# Mergen_Telemetri_Ate_leme.net
KiCad netlist of a schematic drawn in EAGLE
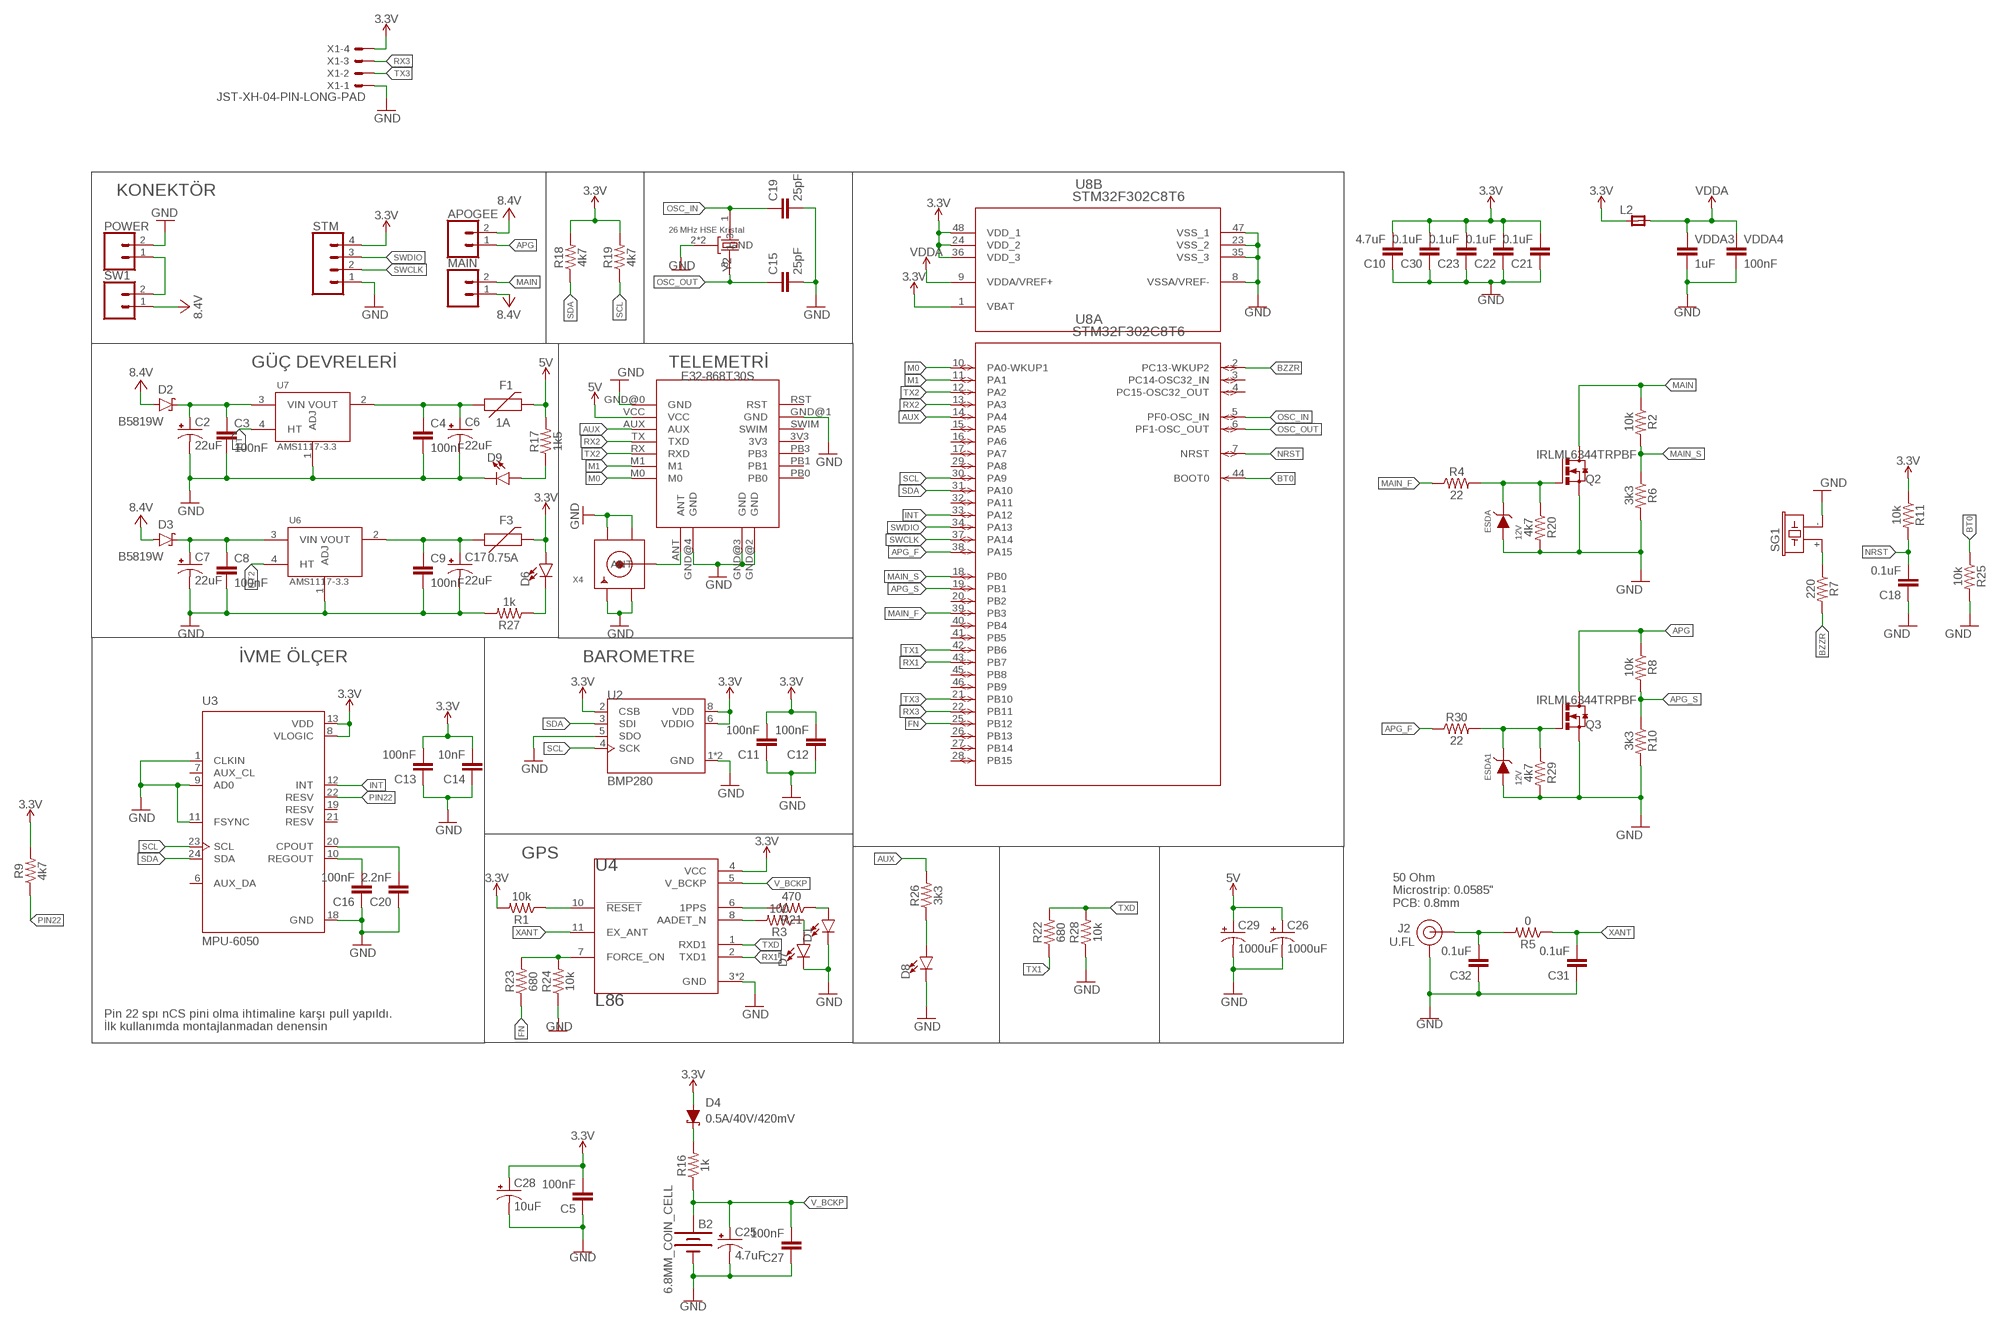
[diagram p0: schematic, sheet 1]

(export (version "E")
  (design (tool "Eeschema 10.0.6"))
  (components
    (comp (ref "APOGEE")
      (value "CONN_023.5MM-NO_SILK")
      (footprint "eagle-import:SCREWTERMINAL-3.5MM-2-NS")
      (libsource (lib "eagle-import") (part "CONN_023.5MM-NO_SILK"))
    )
    (comp (ref "B2")
      (value "6.8MM_COIN_CELL")
      (footprint "eagle-import:BATTCON-6.8MM")
      (libsource (lib "eagle-import") (part "BATTERY-6.8MM_SMD"))
    )
    (comp (ref "C2")
      (value "22uF")
      (footprint "eagle-import:EIA3528")
      (libsource (lib "eagle-import") (part "47UF-POLAR-EIA3528-10V-10%"))
    )
    (comp (ref "C3")
      (value "100nF")
      (footprint "eagle-import:0603")
      (libsource (lib "eagle-import") (part "1.0UF-0603-16V-10%"))
    )
    (comp (ref "C4")
      (value "100nF")
      (footprint "eagle-import:0603")
      (libsource (lib "eagle-import") (part "1.0UF-0603-16V-10%"))
    )
    (comp (ref "C5")
      (value "100nF")
      (footprint "eagle-import:0603")
      (libsource (lib "eagle-import") (part "1.0UF-0603-16V-10%"))
    )
    (comp (ref "C6")
      (value "22uF")
      (footprint "eagle-import:EIA3528")
      (libsource (lib "eagle-import") (part "47UF-POLAR-EIA3528-10V-10%"))
    )
    (comp (ref "C7")
      (value "22uF")
      (footprint "eagle-import:EIA3528")
      (libsource (lib "eagle-import") (part "47UF-POLAR-EIA3528-10V-10%"))
    )
    (comp (ref "C8")
      (value "100nF")
      (footprint "eagle-import:0603")
      (libsource (lib "eagle-import") (part "1.0UF-0603-16V-10%"))
    )
    (comp (ref "C9")
      (value "100nF")
      (footprint "eagle-import:0603")
      (libsource (lib "eagle-import") (part "1.0UF-0603-16V-10%"))
    )
    (comp (ref "C10")
      (value "4.7uF")
      (footprint "eagle-import:0603")
      (libsource (lib "eagle-import") (part "1.0UF-0603-16V-10%"))
    )
    (comp (ref "C11")
      (value "100nF")
      (footprint "eagle-import:0603")
      (libsource (lib "eagle-import") (part "1.0UF-0603-16V-10%"))
    )
    (comp (ref "C12")
      (value "100nF")
      (footprint "eagle-import:0603")
      (libsource (lib "eagle-import") (part "1.0UF-0603-16V-10%"))
    )
    (comp (ref "C13")
      (value "100nF")
      (footprint "eagle-import:0603")
      (libsource (lib "eagle-import") (part "1.0UF-0603-16V-10%"))
    )
    (comp (ref "C14")
      (value "10nF")
      (footprint "eagle-import:0603")
      (libsource (lib "eagle-import") (part "1.0UF-0603-16V-10%"))
    )
    (comp (ref "C15")
      (value "25pF")
      (footprint "eagle-import:0603")
      (libsource (lib "eagle-import") (part "1.0UF-0603-16V-10%"))
    )
    (comp (ref "C16")
      (value "100nF")
      (footprint "eagle-import:0603")
      (libsource (lib "eagle-import") (part "1.0UF-0603-16V-10%"))
    )
    (comp (ref "C17")
      (value "22uF")
      (footprint "eagle-import:EIA3528")
      (libsource (lib "eagle-import") (part "47UF-POLAR-EIA3528-10V-10%"))
    )
    (comp (ref "C18")
      (value "0.1uF")
      (footprint "eagle-import:0603")
      (libsource (lib "eagle-import") (part "1.0UF-0603-16V-10%"))
    )
    (comp (ref "C19")
      (value "25pF")
      (footprint "eagle-import:0603")
      (libsource (lib "eagle-import") (part "1.0UF-0603-16V-10%"))
    )
    (comp (ref "C20")
      (value "2.2nF")
      (footprint "eagle-import:0603")
      (libsource (lib "eagle-import") (part "1.0UF-0603-16V-10%"))
    )
    (comp (ref "C21")
      (value "0.1uF")
      (footprint "eagle-import:0603")
      (libsource (lib "eagle-import") (part "1.0UF-0603-16V-10%"))
    )
    (comp (ref "C22")
      (value "0.1uF")
      (footprint "eagle-import:0603")
      (libsource (lib "eagle-import") (part "1.0UF-0603-16V-10%"))
    )
    (comp (ref "C23")
      (value "0.1uF")
      (footprint "eagle-import:0603")
      (libsource (lib "eagle-import") (part "1.0UF-0603-16V-10%"))
    )
    (comp (ref "C25")
      (value "4.7uF")
      (footprint "eagle-import:EIA3216")
      (libsource (lib "eagle-import") (part "10UF-POLAR-EIA3216-16V-10%(TANT)"))
    )
    (comp (ref "C26")
      (value "1000uF")
      (footprint "eagle-import:150CLZ-1010")
      (libsource (lib "eagle-import") (part "CPOL-US150CLZ-1010"))
    )
    (comp (ref "C27")
      (value "100nF")
      (footprint "eagle-import:0603")
      (libsource (lib "eagle-import") (part "1.0UF-0603-16V-10%"))
    )
    (comp (ref "C28")
      (value "10uF")
      (footprint "eagle-import:EIA3216")
      (libsource (lib "eagle-import") (part "10UF-POLAR-EIA3216-16V-10%(TANT)"))
    )
    (comp (ref "C29")
      (value "1000uF")
      (footprint "eagle-import:150CLZ-1010")
      (libsource (lib "eagle-import") (part "CPOL-US150CLZ-1010"))
    )
    (comp (ref "C30")
      (value "0.1uF")
      (footprint "eagle-import:0603")
      (libsource (lib "eagle-import") (part "1.0UF-0603-16V-10%"))
    )
    (comp (ref "C31")
      (value "0.1uF")
      (footprint "eagle-import:0603")
      (libsource (lib "eagle-import") (part "1.0UF-0603-16V-10%"))
    )
    (comp (ref "C32")
      (value "0.1uF")
      (footprint "eagle-import:0603")
      (libsource (lib "eagle-import") (part "1.0UF-0603-16V-10%"))
    )
    (comp (ref "D1")
      (value "LED0603")
      (footprint "eagle-import:LED-0603")
      (libsource (lib "eagle-import") (part "LED0603"))
    )
    (comp (ref "D2")
      (value "B5819W")
      (footprint "eagle-import:SODFL3718X115")
      (fields (field (name "MANUFACTURER") "ON Semiconductor") (field (name "MPN") "MBR0520LT1G"))
      (libsource (lib "eagle-import") (part "SCHOTTKY_DO-219MBR0520LT1G"))
    )
    (comp (ref "D3")
      (value "B5819W")
      (footprint "eagle-import:SODFL3718X115")
      (fields (field (name "MANUFACTURER") "ON Semiconductor") (field (name "MPN") "MBR0520LT1G"))
      (libsource (lib "eagle-import") (part "SCHOTTKY_DO-219MBR0520LT1G"))
    )
    (comp (ref "D4")
      (value "0.5A/40V/420mV")
      (footprint "eagle-import:SOD-323")
      (libsource (lib "eagle-import") (part "DIODE-SCHOTTKY-PMEG4005EJ"))
    )
    (comp (ref "D6")
      (value "LED0603")
      (footprint "eagle-import:LED-0603")
      (libsource (lib "eagle-import") (part "LED0603"))
    )
    (comp (ref "D7")
      (value "LED0603")
      (footprint "eagle-import:LED-0603")
      (libsource (lib "eagle-import") (part "LED0603"))
    )
    (comp (ref "D8")
      (value "LED0603")
      (footprint "eagle-import:LED-0603")
      (libsource (lib "eagle-import") (part "LED0603"))
    )
    (comp (ref "D9")
      (value "LED0603")
      (footprint "eagle-import:LED-0603")
      (libsource (lib "eagle-import") (part "LED0603"))
    )
    (comp (ref "ESDA")
      (value "12V")
      (footprint "eagle-import:WE-TVSP_DO-214AC_UNIDIRECTIONAL")
      (libsource (lib "eagle-import") (part "WE-TVSP_DO-214AC_400W_UNI_824500102"))
    )
    (comp (ref "ESDA1")
      (value "12V")
      (footprint "eagle-import:WE-TVSP_DO-214AC_UNIDIRECTIONAL")
      (libsource (lib "eagle-import") (part "WE-TVSP_DO-214AC_400W_UNI_824500102"))
    )
    (comp (ref "F1")
      (value "1A")
      (footprint "eagle-import:1206")
      (libsource (lib "eagle-import") (part "PPTC_HALF-AMP"))
    )
    (comp (ref "F3")
      (value "0.75A")
      (footprint "eagle-import:1206")
      (libsource (lib "eagle-import") (part "PPTC_HALF-AMP"))
    )
    (comp (ref "J2")
      (value "U.FL")
      (footprint "eagle-import:U.FL")
      (libsource (lib "eagle-import") (part "U.FL2PIN"))
    )
    (comp (ref "L2")
      (value "RC-MASTER-SMD_FB_0805MP")
      (footprint "eagle-import:RC-MASTER-SMD_L0805MP")
      (libsource (lib "eagle-import") (part "RC-MASTER-SMD_FB_0805MP"))
    )
    (comp (ref "MAIN")
      (value "CONN_023.5MM-NO_SILK")
      (footprint "eagle-import:SCREWTERMINAL-3.5MM-2-NS")
      (libsource (lib "eagle-import") (part "CONN_023.5MM-NO_SILK"))
    )
    (comp (ref "POWER")
      (value "CONN_023.5MM-NO_SILK")
      (footprint "eagle-import:SCREWTERMINAL-3.5MM-2-NS")
      (libsource (lib "eagle-import") (part "CONN_023.5MM-NO_SILK"))
    )
    (comp (ref "Q2")
      (value "IRLML6344TRPBF")
      (footprint "eagle-import:SOT23")
      (fields (field (name "MF") "Infineon"))
      (libsource (lib "eagle-import") (part "IRLML6344TRPBF"))
    )
    (comp (ref "Q3")
      (value "IRLML6344TRPBF")
      (footprint "eagle-import:SOT23")
      (fields (field (name "MF") "Infineon"))
      (libsource (lib "eagle-import") (part "IRLML6344TRPBF"))
    )
    (comp (ref "R1")
      (value "10k")
      (footprint "eagle-import:0603")
      (libsource (lib "eagle-import") (part "SparkFun-Resistors_532_1KOHM-0603-1/10W-1%"))
    )
    (comp (ref "R2")
      (value "10k")
      (footprint "eagle-import:0603")
      (libsource (lib "eagle-import") (part "SparkFun-Resistors_532_1KOHM-0603-1/10W-1%"))
    )
    (comp (ref "R3")
      (value "100")
      (footprint "eagle-import:0603")
      (libsource (lib "eagle-import") (part "SparkFun-Resistors_532_1KOHM-0603-1/10W-1%"))
    )
    (comp (ref "R4")
      (value "22")
      (footprint "eagle-import:0603")
      (libsource (lib "eagle-import") (part "SparkFun-Resistors_532_1KOHM-0603-1/10W-1%"))
    )
    (comp (ref "R5")
      (value "0")
      (footprint "eagle-import:0603")
      (libsource (lib "eagle-import") (part "SparkFun-Resistors_532_1KOHM-0603-1/10W-1%"))
    )
    (comp (ref "R6")
      (value "3k3")
      (footprint "eagle-import:0603")
      (libsource (lib "eagle-import") (part "SparkFun-Resistors_532_1KOHM-0603-1/10W-1%"))
    )
    (comp (ref "R7")
      (value "220")
      (footprint "eagle-import:0603")
      (libsource (lib "eagle-import") (part "SparkFun-Resistors_532_1KOHM-0603-1/10W-1%"))
    )
    (comp (ref "R8")
      (value "10k")
      (footprint "eagle-import:0603")
      (libsource (lib "eagle-import") (part "SparkFun-Resistors_532_1KOHM-0603-1/10W-1%"))
    )
    (comp (ref "R9")
      (value "4k7")
      (footprint "eagle-import:0603")
      (libsource (lib "eagle-import") (part "SparkFun-Resistors_532_1KOHM-0603-1/10W-1%"))
    )
    (comp (ref "R10")
      (value "3k3")
      (footprint "eagle-import:0603")
      (libsource (lib "eagle-import") (part "SparkFun-Resistors_532_1KOHM-0603-1/10W-1%"))
    )
    (comp (ref "R11")
      (value "10k")
      (footprint "eagle-import:0603")
      (libsource (lib "eagle-import") (part "SparkFun-Resistors_532_1KOHM-0603-1/10W-1%"))
    )
    (comp (ref "R16")
      (value "1k")
      (footprint "eagle-import:0603")
      (libsource (lib "eagle-import") (part "1KOHM-0603-1/10W-1%"))
    )
    (comp (ref "R17")
      (value "1k5")
      (footprint "eagle-import:0603")
      (libsource (lib "eagle-import") (part "SparkFun-Resistors_532_1KOHM-0603-1/10W-1%"))
    )
    (comp (ref "R18")
      (value "4k7")
      (footprint "eagle-import:0603")
      (libsource (lib "eagle-import") (part "SparkFun-Resistors_532_1KOHM-0603-1/10W-1%"))
    )
    (comp (ref "R19")
      (value "4k7")
      (footprint "eagle-import:0603")
      (libsource (lib "eagle-import") (part "SparkFun-Resistors_532_1KOHM-0603-1/10W-1%"))
    )
    (comp (ref "R20")
      (value "4k7")
      (footprint "eagle-import:0603")
      (libsource (lib "eagle-import") (part "SparkFun-Resistors_532_1KOHM-0603-1/10W-1%"))
    )
    (comp (ref "R21")
      (value "470")
      (footprint "eagle-import:0603")
      (libsource (lib "eagle-import") (part "SparkFun-Resistors_532_1KOHM-0603-1/10W-1%"))
    )
    (comp (ref "R22")
      (value "680")
      (footprint "eagle-import:0603")
      (libsource (lib "eagle-import") (part "SparkFun-Resistors_532_1KOHM-0603-1/10W-1%"))
    )
    (comp (ref "R23")
      (value "680")
      (footprint "eagle-import:0603")
      (libsource (lib "eagle-import") (part "SparkFun-Resistors_532_1KOHM-0603-1/10W-1%"))
    )
    (comp (ref "R24")
      (value "10k")
      (footprint "eagle-import:0603")
      (libsource (lib "eagle-import") (part "SparkFun-Resistors_532_1KOHM-0603-1/10W-1%"))
    )
    (comp (ref "R25")
      (value "10k")
      (footprint "eagle-import:0603")
      (libsource (lib "eagle-import") (part "SparkFun-Resistors_532_1KOHM-0603-1/10W-1%"))
    )
    (comp (ref "R26")
      (value "3k3")
      (footprint "eagle-import:0603")
      (libsource (lib "eagle-import") (part "SparkFun-Resistors_532_1KOHM-0603-1/10W-1%"))
    )
    (comp (ref "R27")
      (value "1k")
      (footprint "eagle-import:0603")
      (libsource (lib "eagle-import") (part "SparkFun-Resistors_532_1KOHM-0603-1/10W-1%"))
    )
    (comp (ref "R28")
      (value "10k")
      (footprint "eagle-import:0603")
      (libsource (lib "eagle-import") (part "SparkFun-Resistors_532_1KOHM-0603-1/10W-1%"))
    )
    (comp (ref "R29")
      (value "4k7")
      (footprint "eagle-import:0603")
      (libsource (lib "eagle-import") (part "SparkFun-Resistors_532_1KOHM-0603-1/10W-1%"))
    )
    (comp (ref "R30")
      (value "22")
      (footprint "eagle-import:0603")
      (libsource (lib "eagle-import") (part "SparkFun-Resistors_532_1KOHM-0603-1/10W-1%"))
    )
    (comp (ref "SG1")
      (value "F/CM12P")
      (footprint "eagle-import:F_CM12P")
      (libsource (lib "eagle-import") (part "F/CM12P"))
    )
    (comp (ref "STM")
      (value "CONN_04")
      (footprint "eagle-import:1X04")
      (libsource (lib "eagle-import") (part "CONN_04"))
    )
    (comp (ref "SW1")
      (value "CONN_023.5MM-NO_SILK")
      (footprint "eagle-import:SCREWTERMINAL-3.5MM-2-NS")
      (libsource (lib "eagle-import") (part "CONN_023.5MM-NO_SILK"))
    )
    (comp (ref "U2")
      (value "BMP280")
      (footprint "eagle-import:XDCR_BMP280")
      (fields (field (name "MF") "Bosch"))
      (libsource (lib "eagle-import") (part "BMP280"))
    )
    (comp (ref "U3")
      (value "MPU-6050")
      (footprint "eagle-import:QFN50P400X400X95-24N")
      (fields (field (name "MF") "TDK InvenSense"))
      (libsource (lib "eagle-import") (part "MPU-6050"))
    )
    (comp (ref "U4")
      (value "L86")
      (footprint "eagle-import:XCVR_L86")
      (fields (field (name "MF") "Quectel"))
      (libsource (lib "eagle-import") (part "L86"))
    )
    (comp (ref "U5")
      (value "E32-868T30S")
      (footprint "eagle-import:E32-868T30S")
      (libsource (lib "eagle-import") (part "E32-868T30S"))
    )
    (comp (ref "U6")
      (value "AMS1117-3.3")
      (footprint "eagle-import:SOT229P700X180-4N")
      (fields (field (name "MF") "Advanced Monolithic Systems"))
      (libsource (lib "eagle-import") (part "AMS1117-3.3"))
    )
    (comp (ref "U7")
      (value "AMS1117-3.3")
      (footprint "eagle-import:SOT229P700X180-4N")
      (fields (field (name "MF") "Advanced Monolithic Systems"))
      (libsource (lib "eagle-import") (part "AMS1117-3.3"))
    )
    (comp (ref "U8")
      (value "STM32F302C8T6")
      (footprint "eagle-import:LQFP48-7X7MM")
      (fields (field (name "COPYRIGHT") "Copyright (C) 2018 Accelerated Designs. All rights reserved"))
      (libsource (lib "eagle-import") (part "STM32F302C8T6"))
    )
    (comp (ref "VDDA3")
      (value "1uF")
      (footprint "eagle-import:0603")
      (libsource (lib "eagle-import") (part "0.1UF-0603-25V-(+80/-20%)"))
    )
    (comp (ref "VDDA4")
      (value "100nF")
      (footprint "eagle-import:0603")
      (libsource (lib "eagle-import") (part "0.1UF-0603-25V-(+80/-20%)"))
    )
    (comp (ref "X1")
      (value "JST-XH-04-PIN-LONG-PAD")
      (footprint "eagle-import:JST-XH-04-PACKAGE-LONG-PAD")
      (libsource (lib "eagle-import") (part "JST-XH-04-PIN-LONG-PAD"))
    )
    (comp (ref "X4")
      (value "SMACONNECTOR")
      (footprint "eagle-import:SMA90_DIP")
      (libsource (lib "eagle-import") (part "SMACONNECTOR"))
    )
    (comp (ref "Y2")
      (value "ABM3B-26.000MHZ-10-1-U-T")
      (footprint "eagle-import:OSCCC500X320X110-4N")
      (fields (field (name "MF") "Abracon"))
      (libsource (lib "eagle-import") (part "ABM3B-26.000MHZ-10-1-U-T"))
    )
  )
  (nets
    (net (code "1") (name "3.3V") (class "Default")
      (node (ref "C10") (pin "2") (pinfunction "2_2") (pintype "passive"))
      (node (ref "C11") (pin "2") (pinfunction "2_2") (pintype "passive"))
      (node (ref "C12") (pin "2") (pinfunction "2_2") (pintype "passive"))
      (node (ref "C13") (pin "2") (pinfunction "2_2") (pintype "passive"))
      (node (ref "C14") (pin "2") (pinfunction "2_2") (pintype "passive"))
      (node (ref "C21") (pin "2") (pinfunction "2_2") (pintype "passive"))
      (node (ref "C22") (pin "2") (pinfunction "2_2") (pintype "passive"))
      (node (ref "C23") (pin "2") (pinfunction "2_2") (pintype "passive"))
      (node (ref "C28") (pin "+") (pinfunction "+_+") (pintype "passive"))
      (node (ref "C30") (pin "2") (pinfunction "2_2") (pintype "passive"))
      (node (ref "C5") (pin "2") (pinfunction "2_2") (pintype "passive"))
      (node (ref "D4") (pin "A") (pinfunction "A_A") (pintype "passive"))
      (node (ref "D6") (pin "A") (pinfunction "A_A") (pintype "passive"))
      (node (ref "F3") (pin "2") (pinfunction "2_2") (pintype "bidirectional"))
      (node (ref "L2") (pin "1") (pinfunction "1_1") (pintype "passive"))
      (node (ref "R1") (pin "2") (pinfunction "2_2") (pintype "passive"))
      (node (ref "R11") (pin "1") (pinfunction "1_1") (pintype "passive"))
      (node (ref "R18") (pin "2") (pinfunction "2_2") (pintype "passive"))
      (node (ref "R19") (pin "2") (pinfunction "2_2") (pintype "passive"))
      (node (ref "R9") (pin "2") (pinfunction "2_2") (pintype "passive"))
      (node (ref "STM") (pin "4") (pinfunction "4_4") (pintype "passive"))
      (node (ref "U2") (pin "2") (pinfunction "CSB_2") (pintype "input"))
      (node (ref "U2") (pin "6") (pinfunction "VDDIO_6") (pintype "power_in"))
      (node (ref "U2") (pin "8") (pinfunction "VDD_8") (pintype "power_in"))
      (node (ref "U3") (pin "13") (pinfunction "VDD_13") (pintype "power_in"))
      (node (ref "U3") (pin "8") (pinfunction "VLOGIC_8") (pintype "power_in"))
      (node (ref "U4") (pin "4") (pinfunction "VCC_4") (pintype "power_in"))
      (node (ref "U8") (pin "1") (pinfunction "VBAT_1") (pintype "power_in"))
      (node (ref "U8") (pin "24") (pinfunction "VDD_2_24") (pintype "power_in"))
      (node (ref "U8") (pin "36") (pinfunction "VDD_3_36") (pintype "power_in"))
      (node (ref "U8") (pin "48") (pinfunction "VDD_1_48") (pintype "power_in"))
      (node (ref "X1") (pin "4") (pinfunction "S_4") (pintype "passive"))
    )
    (net (code "2") (name "5V") (class "Default")
      (node (ref "C26") (pin "+") (pinfunction "+_+") (pintype "passive"))
      (node (ref "C29") (pin "+") (pinfunction "+_+") (pintype "passive"))
      (node (ref "F1") (pin "2") (pinfunction "2_2") (pintype "bidirectional"))
      (node (ref "R17") (pin "2") (pinfunction "2_2") (pintype "passive"))
      (node (ref "U5") (pin "VCC") (pinfunction "VCC_VCC") (pintype "bidirectional"))
    )
    (net (code "3") (name "8.4V") (class "Default")
      (node (ref "APOGEE") (pin "2") (pinfunction "2_2") (pintype "passive"))
      (node (ref "D2") (pin "2") (pinfunction "A_2") (pintype "passive"))
      (node (ref "D3") (pin "2") (pinfunction "A_2") (pintype "passive"))
      (node (ref "MAIN") (pin "1") (pinfunction "1_1") (pintype "passive"))
      (node (ref "SW1") (pin "1") (pinfunction "1_1") (pintype "passive"))
    )
    (net (code "4") (name "APG") (class "Default")
      (node (ref "APOGEE") (pin "1") (pinfunction "1_1") (pintype "passive"))
      (node (ref "Q3") (pin "3") (pinfunction "D_3") (pintype "passive"))
      (node (ref "R8") (pin "1") (pinfunction "1_1") (pintype "passive"))
    )
    (net (code "5") (name "APG_F") (class "Default")
      (node (ref "R30") (pin "1") (pinfunction "1_1") (pintype "passive"))
      (node (ref "U8") (pin "38") (pinfunction "PA15_38") (pintype "bidirectional"))
    )
    (net (code "6") (name "APG_S") (class "Default")
      (node (ref "R10") (pin "1") (pinfunction "1_1") (pintype "passive"))
      (node (ref "R8") (pin "2") (pinfunction "2_2") (pintype "passive"))
      (node (ref "U8") (pin "19") (pinfunction "PB1_19") (pintype "bidirectional"))
    )
    (net (code "7") (name "AUX") (class "Default")
      (node (ref "R26") (pin "2") (pinfunction "2_2") (pintype "passive"))
      (node (ref "U5") (pin "AUX") (pinfunction "AUX_AUX") (pintype "bidirectional"))
      (node (ref "U8") (pin "14") (pinfunction "PA4_14") (pintype "bidirectional"))
    )
    (net (code "8") (name "BT0") (class "Default")
      (node (ref "R25") (pin "1") (pinfunction "1_1") (pintype "passive"))
      (node (ref "U8") (pin "44") (pinfunction "BOOT0_44") (pintype "input"))
    )
    (net (code "9") (name "BZZR") (class "Default")
      (node (ref "R7") (pin "2") (pinfunction "2_2") (pintype "passive"))
      (node (ref "U8") (pin "2") (pinfunction "PC13-WKUP2_2") (pintype "bidirectional"))
    )
    (net (code "10") (name "FN") (class "Default")
      (node (ref "R23") (pin "1") (pinfunction "1_1") (pintype "passive"))
      (node (ref "U8") (pin "25") (pinfunction "PB12_25") (pintype "bidirectional"))
    )
    (net (code "11") (name "GND") (class "Default")
      (node (ref "B2") (pin "-") (pinfunction "-_-") (pintype "power_in"))
      (node (ref "C10") (pin "1") (pinfunction "1_1") (pintype "passive"))
      (node (ref "C11") (pin "1") (pinfunction "1_1") (pintype "passive"))
      (node (ref "C12") (pin "1") (pinfunction "1_1") (pintype "passive"))
      (node (ref "C13") (pin "1") (pinfunction "1_1") (pintype "passive"))
      (node (ref "C14") (pin "1") (pinfunction "1_1") (pintype "passive"))
      (node (ref "C15") (pin "2") (pinfunction "2_2") (pintype "passive"))
      (node (ref "C16") (pin "1") (pinfunction "1_1") (pintype "passive"))
      (node (ref "C17") (pin "C") (pinfunction "-_C") (pintype "passive"))
      (node (ref "C18") (pin "1") (pinfunction "1_1") (pintype "passive"))
      (node (ref "C19") (pin "2") (pinfunction "2_2") (pintype "passive"))
      (node (ref "C2") (pin "C") (pinfunction "-_C") (pintype "passive"))
      (node (ref "C20") (pin "1") (pinfunction "1_1") (pintype "passive"))
      (node (ref "C21") (pin "1") (pinfunction "1_1") (pintype "passive"))
      (node (ref "C22") (pin "1") (pinfunction "1_1") (pintype "passive"))
      (node (ref "C23") (pin "1") (pinfunction "1_1") (pintype "passive"))
      (node (ref "C25") (pin "-") (pinfunction "-_-") (pintype "passive"))
      (node (ref "C26") (pin "-") (pinfunction "-_-") (pintype "passive"))
      (node (ref "C27") (pin "1") (pinfunction "1_1") (pintype "passive"))
      (node (ref "C28") (pin "-") (pinfunction "-_-") (pintype "passive"))
      (node (ref "C29") (pin "-") (pinfunction "-_-") (pintype "passive"))
      (node (ref "C3") (pin "2") (pinfunction "2_2") (pintype "passive"))
      (node (ref "C30") (pin "1") (pinfunction "1_1") (pintype "passive"))
      (node (ref "C31") (pin "1") (pinfunction "1_1") (pintype "passive"))
      (node (ref "C32") (pin "1") (pinfunction "1_1") (pintype "passive"))
      (node (ref "C4") (pin "2") (pinfunction "2_2") (pintype "passive"))
      (node (ref "C5") (pin "1") (pinfunction "1_1") (pintype "passive"))
      (node (ref "C6") (pin "C") (pinfunction "-_C") (pintype "passive"))
      (node (ref "C7") (pin "C") (pinfunction "-_C") (pintype "passive"))
      (node (ref "C8") (pin "2") (pinfunction "2_2") (pintype "passive"))
      (node (ref "C9") (pin "2") (pinfunction "2_2") (pintype "passive"))
      (node (ref "D1") (pin "C") (pinfunction "C_C") (pintype "passive"))
      (node (ref "D7") (pin "C") (pinfunction "C_C") (pintype "passive"))
      (node (ref "D8") (pin "C") (pinfunction "C_C") (pintype "passive"))
      (node (ref "D9") (pin "C") (pinfunction "C_C") (pintype "passive"))
      (node (ref "ESDA") (pin "2") (pinfunction "A_2") (pintype "passive"))
      (node (ref "ESDA1") (pin "2") (pinfunction "A_2") (pintype "passive"))
      (node (ref "J2") (pin "1") (pinfunction "GND_1") (pintype "bidirectional"))
      (node (ref "J2") (pin "2") (pinfunction "GND_2") (pintype "bidirectional"))
      (node (ref "POWER") (pin "2") (pinfunction "2_2") (pintype "passive"))
      (node (ref "Q2") (pin "2") (pinfunction "S_2") (pintype "passive"))
      (node (ref "Q3") (pin "2") (pinfunction "S_2") (pintype "passive"))
      (node (ref "R10") (pin "2") (pinfunction "2_2") (pintype "passive"))
      (node (ref "R20") (pin "2") (pinfunction "2_2") (pintype "passive"))
      (node (ref "R24") (pin "1") (pinfunction "1_1") (pintype "passive"))
      (node (ref "R25") (pin "2") (pinfunction "2_2") (pintype "passive"))
      (node (ref "R27") (pin "2") (pinfunction "2_2") (pintype "passive"))
      (node (ref "R28") (pin "1") (pinfunction "1_1") (pintype "passive"))
      (node (ref "R29") (pin "2") (pinfunction "2_2") (pintype "passive"))
      (node (ref "R6") (pin "2") (pinfunction "2_2") (pintype "passive"))
      (node (ref "SG1") (pin "-") (pinfunction "2_-") (pintype "passive"))
      (node (ref "STM") (pin "1") (pinfunction "1_1") (pintype "passive"))
      (node (ref "U2") (pin "1") (pinfunction "GND_1") (pintype "power_in"))
      (node (ref "U2") (pin "5") (pinfunction "SDO_5") (pintype "bidirectional"))
      (node (ref "U2") (pin "7") (pinfunction "GND_7") (pintype "power_in"))
      (node (ref "U3") (pin "1") (pinfunction "CLKIN_1") (pintype "input"))
      (node (ref "U3") (pin "11") (pinfunction "FSYNC_11") (pintype "input"))
      (node (ref "U3") (pin "18") (pinfunction "GND_18") (pintype "power_in"))
      (node (ref "U3") (pin "9") (pinfunction "AD0_9") (pintype "input"))
      (node (ref "U4") (pin "12") (pinfunction "GND_12") (pintype "passive"))
      (node (ref "U4") (pin "3") (pinfunction "GND_3") (pintype "passive"))
      (node (ref "U5") (pin "GND@0") (pinfunction "GND_GND@0") (pintype "bidirectional"))
      (node (ref "U5") (pin "GND@1") (pinfunction "GND_GND@1") (pintype "bidirectional"))
      (node (ref "U5") (pin "GND@2") (pinfunction "GND_GND@2") (pintype "bidirectional"))
      (node (ref "U5") (pin "GND@3") (pinfunction "GND_GND@3") (pintype "bidirectional"))
      (node (ref "U5") (pin "GND@4") (pinfunction "GND_GND@4") (pintype "bidirectional"))
      (node (ref "U6") (pin "1") (pinfunction "ADJ_1") (pintype "power_in"))
      (node (ref "U7") (pin "1") (pinfunction "ADJ_1") (pintype "power_in"))
      (node (ref "U8") (pin "23") (pinfunction "VSS_2_23") (pintype "power_in"))
      (node (ref "U8") (pin "35") (pinfunction "VSS_3_35") (pintype "power_in"))
      (node (ref "U8") (pin "47") (pinfunction "VSS_1_47") (pintype "power_in"))
      (node (ref "U8") (pin "8") (pinfunction "VSSA/VREF-_8") (pintype "power_in"))
      (node (ref "VDDA3") (pin "2") (pinfunction "2_2") (pintype "passive"))
      (node (ref "VDDA4") (pin "2") (pinfunction "2_2") (pintype "passive"))
      (node (ref "X1") (pin "1") (pinfunction "S_1") (pintype "passive"))
      (node (ref "X4") (pin "GND1") (pinfunction "GND1_GND1") (pintype "power_in"))
      (node (ref "X4") (pin "GND2") (pinfunction "GND2_GND2") (pintype "power_in"))
      (node (ref "X4") (pin "GND3") (pinfunction "GND3_GND3") (pintype "power_in"))
      (node (ref "X4") (pin "GND4") (pinfunction "GND4_GND4") (pintype "power_in"))
      (node (ref "Y2") (pin "2") (pinfunction "GND_2") (pintype "passive"))
      (node (ref "Y2") (pin "4") (pinfunction "GND_4") (pintype "passive"))
    )
    (net (code "12") (name "HT") (class "Default")
      (node (ref "U7") (pin "4") (pinfunction "HT_4") (pintype "bidirectional"))
    )
    (net (code "13") (name "HT2") (class "Default")
      (node (ref "U6") (pin "4") (pinfunction "HT_4") (pintype "bidirectional"))
    )
    (net (code "14") (name "INT") (class "Default")
      (node (ref "U3") (pin "12") (pinfunction "INT_12") (pintype "output"))
      (node (ref "U8") (pin "33") (pinfunction "PA12_33") (pintype "bidirectional"))
    )
    (net (code "15") (name "M0") (class "Default")
      (node (ref "U5") (pin "M0") (pinfunction "M0_M0") (pintype "bidirectional"))
      (node (ref "U8") (pin "10") (pinfunction "PA0-WKUP1_10") (pintype "bidirectional"))
    )
    (net (code "16") (name "M1") (class "Default")
      (node (ref "U5") (pin "M1") (pinfunction "M1_M1") (pintype "bidirectional"))
      (node (ref "U8") (pin "11") (pinfunction "PA1_11") (pintype "bidirectional"))
    )
    (net (code "17") (name "MAIN") (class "Default")
      (node (ref "MAIN") (pin "2") (pinfunction "2_2") (pintype "passive"))
      (node (ref "Q2") (pin "3") (pinfunction "D_3") (pintype "passive"))
      (node (ref "R2") (pin "1") (pinfunction "1_1") (pintype "passive"))
    )
    (net (code "18") (name "MAIN_F") (class "Default")
      (node (ref "R4") (pin "1") (pinfunction "1_1") (pintype "passive"))
      (node (ref "U8") (pin "39") (pinfunction "PB3_39") (pintype "bidirectional"))
    )
    (net (code "19") (name "MAIN_S") (class "Default")
      (node (ref "R2") (pin "2") (pinfunction "2_2") (pintype "passive"))
      (node (ref "R6") (pin "1") (pinfunction "1_1") (pintype "passive"))
      (node (ref "U8") (pin "18") (pinfunction "PB0_18") (pintype "bidirectional"))
    )
    (net (code "20") (name "NRST") (class "Default")
      (node (ref "C18") (pin "2") (pinfunction "2_2") (pintype "passive"))
      (node (ref "R11") (pin "2") (pinfunction "2_2") (pintype "passive"))
      (node (ref "U8") (pin "7") (pinfunction "NRST_7") (pintype "bidirectional"))
    )
    (net (code "21") (name "Net-(C2-+)") (class "Default")
      (node (ref "C2") (pin "A") (pinfunction "+_A") (pintype "passive"))
      (node (ref "C3") (pin "1") (pinfunction "1_1") (pintype "passive"))
      (node (ref "D2") (pin "1") (pinfunction "C_1") (pintype "passive"))
      (node (ref "U7") (pin "3") (pinfunction "VIN_3") (pintype "input"))
    )
    (net (code "22") (name "Net-(C6-+)") (class "Default")
      (node (ref "C4") (pin "1") (pinfunction "1_1") (pintype "passive"))
      (node (ref "C6") (pin "A") (pinfunction "+_A") (pintype "passive"))
      (node (ref "F1") (pin "1") (pinfunction "1_1") (pintype "bidirectional"))
      (node (ref "U7") (pin "2") (pinfunction "VOUT_2") (pintype "output"))
    )
    (net (code "23") (name "Net-(C7-+)") (class "Default")
      (node (ref "C7") (pin "A") (pinfunction "+_A") (pintype "passive"))
      (node (ref "C8") (pin "1") (pinfunction "1_1") (pintype "passive"))
      (node (ref "D3") (pin "1") (pinfunction "C_1") (pintype "passive"))
      (node (ref "U6") (pin "3") (pinfunction "VIN_3") (pintype "input"))
    )
    (net (code "24") (name "Net-(C17-+)") (class "Default")
      (node (ref "C17") (pin "A") (pinfunction "+_A") (pintype "passive"))
      (node (ref "C9") (pin "1") (pinfunction "1_1") (pintype "passive"))
      (node (ref "F3") (pin "1") (pinfunction "1_1") (pintype "bidirectional"))
      (node (ref "U6") (pin "2") (pinfunction "VOUT_2") (pintype "output"))
    )
    (net (code "25") (name "Net-(D1-PadA)") (class "Default")
      (node (ref "D1") (pin "A") (pinfunction "A_A") (pintype "passive"))
      (node (ref "R21") (pin "1") (pinfunction "1_1") (pintype "passive"))
    )
    (net (code "26") (name "Net-(D4-PadC)") (class "Default")
      (node (ref "D4") (pin "C") (pinfunction "C_C") (pintype "passive"))
      (node (ref "R16") (pin "2") (pinfunction "2_2") (pintype "passive"))
    )
    (net (code "27") (name "Net-(D6-PadC)") (class "Default")
      (node (ref "D6") (pin "C") (pinfunction "C_C") (pintype "passive"))
      (node (ref "R27") (pin "1") (pinfunction "1_1") (pintype "passive"))
    )
    (net (code "28") (name "Net-(D7-PadA)") (class "Default")
      (node (ref "D7") (pin "A") (pinfunction "A_A") (pintype "passive"))
      (node (ref "R3") (pin "1") (pinfunction "1_1") (pintype "passive"))
    )
    (net (code "29") (name "Net-(D8-PadA)") (class "Default")
      (node (ref "D8") (pin "A") (pinfunction "A_A") (pintype "passive"))
      (node (ref "R26") (pin "1") (pinfunction "1_1") (pintype "passive"))
    )
    (net (code "30") (name "Net-(D9-PadA)") (class "Default")
      (node (ref "D9") (pin "A") (pinfunction "A_A") (pintype "passive"))
      (node (ref "R17") (pin "1") (pinfunction "1_1") (pintype "passive"))
    )
    (net (code "31") (name "Net-(ESDA-C)") (class "Default")
      (node (ref "ESDA") (pin "1") (pinfunction "C_1") (pintype "passive"))
      (node (ref "Q2") (pin "1") (pinfunction "G_1") (pintype "passive"))
      (node (ref "R20") (pin "1") (pinfunction "1_1") (pintype "passive"))
      (node (ref "R4") (pin "2") (pinfunction "2_2") (pintype "passive"))
    )
    (net (code "32") (name "Net-(ESDA1-C)") (class "Default")
      (node (ref "ESDA1") (pin "1") (pinfunction "C_1") (pintype "passive"))
      (node (ref "Q3") (pin "1") (pinfunction "G_1") (pintype "passive"))
      (node (ref "R29") (pin "1") (pinfunction "1_1") (pintype "passive"))
      (node (ref "R30") (pin "2") (pinfunction "2_2") (pintype "passive"))
    )
    (net (code "33") (name "Net-(J2-SIGNAL)") (class "Default")
      (node (ref "C32") (pin "2") (pinfunction "2_2") (pintype "passive"))
      (node (ref "J2") (pin "FEED") (pinfunction "SIGNAL_FEED") (pintype "bidirectional"))
      (node (ref "R5") (pin "2") (pinfunction "2_2") (pintype "passive"))
    )
    (net (code "34") (name "Net-(POWER-Pad1)") (class "Default")
      (node (ref "POWER") (pin "1") (pinfunction "1_1") (pintype "passive"))
      (node (ref "SW1") (pin "2") (pinfunction "2_2") (pintype "passive"))
    )
    (net (code "35") (name "Net-(SG1-1)") (class "Default")
      (node (ref "R7") (pin "1") (pinfunction "1_1") (pintype "passive"))
      (node (ref "SG1") (pin "+") (pinfunction "1_+") (pintype "passive"))
    )
    (net (code "36") (name "Net-(U3-CPOUT)") (class "Default")
      (node (ref "C20") (pin "2") (pinfunction "2_2") (pintype "passive"))
      (node (ref "U3") (pin "20") (pinfunction "CPOUT_20") (pintype "passive"))
    )
    (net (code "37") (name "Net-(U3-REGOUT)") (class "Default")
      (node (ref "C16") (pin "2") (pinfunction "2_2") (pintype "passive"))
      (node (ref "U3") (pin "10") (pinfunction "REGOUT_10") (pintype "passive"))
    )
    (net (code "38") (name "Net-(U4-1PPS)") (class "Default")
      (node (ref "R21") (pin "2") (pinfunction "2_2") (pintype "passive"))
      (node (ref "U4") (pin "6") (pinfunction "1PPS_6") (pintype "output"))
    )
    (net (code "39") (name "Net-(U4-AADET_N)") (class "Default")
      (node (ref "R3") (pin "2") (pinfunction "2_2") (pintype "passive"))
      (node (ref "U4") (pin "8") (pinfunction "AADET_N_8") (pintype "output"))
    )
    (net (code "40") (name "Net-(U4-FORCE_ON)") (class "Default")
      (node (ref "R23") (pin "2") (pinfunction "2_2") (pintype "passive"))
      (node (ref "R24") (pin "2") (pinfunction "2_2") (pintype "passive"))
      (node (ref "U4") (pin "7") (pinfunction "FORCE_ON_7") (pintype "input"))
    )
    (net (code "41") (name "Net-(U4-~{RESET})") (class "Default")
      (node (ref "R1") (pin "1") (pinfunction "1_1") (pintype "passive"))
      (node (ref "U4") (pin "10") (pinfunction "~{RESET}_10") (pintype "input"))
    )
    (net (code "42") (name "Net-(X4-ANT)") (class "Default")
      (node (ref "U5") (pin "ANT") (pinfunction "ANT_ANT") (pintype "bidirectional"))
      (node (ref "X4") (pin "ANTENNA") (pinfunction "ANT_ANTENNA") (pintype "bidirectional"))
    )
    (net (code "43") (name "OSC_IN") (class "Default")
      (node (ref "C19") (pin "1") (pinfunction "1_1") (pintype "passive"))
      (node (ref "U8") (pin "5") (pinfunction "PF0-OSC_IN_5") (pintype "bidirectional"))
      (node (ref "Y2") (pin "1") (pinfunction "1_1") (pintype "passive"))
    )
    (net (code "44") (name "OSC_OUT") (class "Default")
      (node (ref "C15") (pin "1") (pinfunction "1_1") (pintype "passive"))
      (node (ref "U8") (pin "6") (pinfunction "PF1-OSC_OUT_6") (pintype "bidirectional"))
      (node (ref "Y2") (pin "3") (pinfunction "3_3") (pintype "passive"))
    )
    (net (code "45") (name "PIN22") (class "Default")
      (node (ref "R9") (pin "1") (pinfunction "1_1") (pintype "passive"))
      (node (ref "U3") (pin "22") (pinfunction "RESV_22") (pintype "passive"))
    )
    (net (code "46") (name "RX1") (class "Default")
      (node (ref "U4") (pin "2") (pinfunction "TXD1_2") (pintype "output"))
      (node (ref "U8") (pin "43") (pinfunction "PB7_43") (pintype "bidirectional"))
    )
    (net (code "47") (name "RX2") (class "Default")
      (node (ref "U5") (pin "TX") (pinfunction "TXD_TX") (pintype "bidirectional"))
      (node (ref "U8") (pin "13") (pinfunction "PA3_13") (pintype "bidirectional"))
    )
    (net (code "48") (name "RX3") (class "Default")
      (node (ref "U8") (pin "22") (pinfunction "PB11_22") (pintype "bidirectional"))
      (node (ref "X1") (pin "3") (pinfunction "S_3") (pintype "passive"))
    )
    (net (code "49") (name "SCL") (class "Default")
      (node (ref "R19") (pin "1") (pinfunction "1_1") (pintype "passive"))
      (node (ref "U2") (pin "4") (pinfunction "SCK_4") (pintype "input"))
      (node (ref "U3") (pin "23") (pinfunction "SCL_23") (pintype "input"))
      (node (ref "U8") (pin "30") (pinfunction "PA9_30") (pintype "bidirectional"))
    )
    (net (code "50") (name "SDA") (class "Default")
      (node (ref "R18") (pin "1") (pinfunction "1_1") (pintype "passive"))
      (node (ref "U2") (pin "3") (pinfunction "SDI_3") (pintype "bidirectional"))
      (node (ref "U3") (pin "24") (pinfunction "SDA_24") (pintype "bidirectional"))
      (node (ref "U8") (pin "31") (pinfunction "PA10_31") (pintype "bidirectional"))
    )
    (net (code "51") (name "SWCLK") (class "Default")
      (node (ref "STM") (pin "2") (pinfunction "2_2") (pintype "passive"))
      (node (ref "U8") (pin "37") (pinfunction "PA14_37") (pintype "bidirectional"))
    )
    (net (code "52") (name "SWDIO") (class "Default")
      (node (ref "STM") (pin "3") (pinfunction "3_3") (pintype "passive"))
      (node (ref "U8") (pin "34") (pinfunction "PA13_34") (pintype "bidirectional"))
    )
    (net (code "53") (name "TX1") (class "Default")
      (node (ref "R22") (pin "1") (pinfunction "1_1") (pintype "passive"))
      (node (ref "U8") (pin "42") (pinfunction "PB6_42") (pintype "bidirectional"))
    )
    (net (code "54") (name "TX2") (class "Default")
      (node (ref "U5") (pin "RX") (pinfunction "RXD_RX") (pintype "bidirectional"))
      (node (ref "U8") (pin "12") (pinfunction "PA2_12") (pintype "bidirectional"))
    )
    (net (code "55") (name "TX3") (class "Default")
      (node (ref "U8") (pin "21") (pinfunction "PB10_21") (pintype "bidirectional"))
      (node (ref "X1") (pin "2") (pinfunction "S_2") (pintype "passive"))
    )
    (net (code "56") (name "TXD") (class "Default")
      (node (ref "R22") (pin "2") (pinfunction "2_2") (pintype "passive"))
      (node (ref "R28") (pin "2") (pinfunction "2_2") (pintype "passive"))
      (node (ref "U4") (pin "1") (pinfunction "RXD1_1") (pintype "input"))
    )
    (net (code "57") (name "VDDA") (class "Default")
      (node (ref "L2") (pin "2") (pinfunction "2_2") (pintype "passive"))
      (node (ref "U8") (pin "9") (pinfunction "VDDA/VREF+_9") (pintype "power_in"))
      (node (ref "VDDA3") (pin "1") (pinfunction "1_1") (pintype "passive"))
      (node (ref "VDDA4") (pin "1") (pinfunction "1_1") (pintype "passive"))
    )
    (net (code "58") (name "V_BCKP") (class "Default")
      (node (ref "B2") (pin "+") (pinfunction "+_+") (pintype "power_in"))
      (node (ref "C25") (pin "+") (pinfunction "+_+") (pintype "passive"))
      (node (ref "C27") (pin "2") (pinfunction "2_2") (pintype "passive"))
      (node (ref "R16") (pin "1") (pinfunction "1_1") (pintype "passive"))
      (node (ref "U4") (pin "5") (pinfunction "V_BCKP_5") (pintype "power_in"))
    )
    (net (code "59") (name "XANT") (class "Default")
      (node (ref "C31") (pin "2") (pinfunction "2_2") (pintype "passive"))
      (node (ref "R5") (pin "1") (pinfunction "1_1") (pintype "passive"))
      (node (ref "U4") (pin "11") (pinfunction "EX_ANT_11") (pintype "input"))
    )
    (net (code "60") (name "unconnected-(U3-AUX_CL-Pad7)") (class "Default")
      (node (ref "U3") (pin "7") (pinfunction "AUX_CL_7") (pintype "input"))
    )
    (net (code "61") (name "unconnected-(U3-AUX_DA-Pad6)") (class "Default")
      (node (ref "U3") (pin "6") (pinfunction "AUX_DA_6") (pintype "bidirectional"))
    )
    (net (code "62") (name "unconnected-(U3-RESV-Pad19)") (class "Default")
      (node (ref "U3") (pin "19") (pinfunction "RESV_19") (pintype "passive"))
    )
    (net (code "63") (name "unconnected-(U3-RESV-Pad21)") (class "Default")
      (node (ref "U3") (pin "21") (pinfunction "RESV_21") (pintype "passive"))
    )
    (net (code "64") (name "unconnected-(U5-Pad3V3)") (class "Default")
      (node (ref "U5") (pin "3V3") (pinfunction "3V3_3V3") (pintype "bidirectional"))
    )
    (net (code "65") (name "unconnected-(U5-PadPB0)") (class "Default")
      (node (ref "U5") (pin "PB0") (pinfunction "PB0_PB0") (pintype "bidirectional"))
    )
    (net (code "66") (name "unconnected-(U5-PadPB1)") (class "Default")
      (node (ref "U5") (pin "PB1") (pinfunction "PB1_PB1") (pintype "bidirectional"))
    )
    (net (code "67") (name "unconnected-(U5-PadPB3)") (class "Default")
      (node (ref "U5") (pin "PB3") (pinfunction "PB3_PB3") (pintype "bidirectional"))
    )
    (net (code "68") (name "unconnected-(U5-PadRST)") (class "Default")
      (node (ref "U5") (pin "RST") (pinfunction "RST_RST") (pintype "bidirectional"))
    )
    (net (code "69") (name "unconnected-(U5-PadSWIM)") (class "Default")
      (node (ref "U5") (pin "SWIM") (pinfunction "SWIM_SWIM") (pintype "bidirectional"))
    )
    (net (code "70") (name "unconnected-(U8A-PA5-Pad15)") (class "Default")
      (node (ref "U8") (pin "15") (pinfunction "PA5_15") (pintype "bidirectional"))
    )
    (net (code "71") (name "unconnected-(U8A-PA6-Pad16)") (class "Default")
      (node (ref "U8") (pin "16") (pinfunction "PA6_16") (pintype "bidirectional"))
    )
    (net (code "72") (name "unconnected-(U8A-PA7-Pad17)") (class "Default")
      (node (ref "U8") (pin "17") (pinfunction "PA7_17") (pintype "bidirectional"))
    )
    (net (code "73") (name "unconnected-(U8A-PA8-Pad29)") (class "Default")
      (node (ref "U8") (pin "29") (pinfunction "PA8_29") (pintype "bidirectional"))
    )
    (net (code "74") (name "unconnected-(U8A-PA11-Pad32)") (class "Default")
      (node (ref "U8") (pin "32") (pinfunction "PA11_32") (pintype "bidirectional"))
    )
    (net (code "75") (name "unconnected-(U8A-PB2-Pad20)") (class "Default")
      (node (ref "U8") (pin "20") (pinfunction "PB2_20") (pintype "bidirectional"))
    )
    (net (code "76") (name "unconnected-(U8A-PB4-Pad40)") (class "Default")
      (node (ref "U8") (pin "40") (pinfunction "PB4_40") (pintype "bidirectional"))
    )
    (net (code "77") (name "unconnected-(U8A-PB5-Pad41)") (class "Default")
      (node (ref "U8") (pin "41") (pinfunction "PB5_41") (pintype "bidirectional"))
    )
    (net (code "78") (name "unconnected-(U8A-PB8-Pad45)") (class "Default")
      (node (ref "U8") (pin "45") (pinfunction "PB8_45") (pintype "bidirectional"))
    )
    (net (code "79") (name "unconnected-(U8A-PB9-Pad46)") (class "Default")
      (node (ref "U8") (pin "46") (pinfunction "PB9_46") (pintype "bidirectional"))
    )
    (net (code "80") (name "unconnected-(U8A-PB13-Pad26)") (class "Default")
      (node (ref "U8") (pin "26") (pinfunction "PB13_26") (pintype "bidirectional"))
    )
    (net (code "81") (name "unconnected-(U8A-PB14-Pad27)") (class "Default")
      (node (ref "U8") (pin "27") (pinfunction "PB14_27") (pintype "bidirectional"))
    )
    (net (code "82") (name "unconnected-(U8A-PB15-Pad28)") (class "Default")
      (node (ref "U8") (pin "28") (pinfunction "PB15_28") (pintype "bidirectional"))
    )
    (net (code "83") (name "unconnected-(U8A-PC14-OSC32_IN-Pad3)") (class "Default")
      (node (ref "U8") (pin "3") (pinfunction "PC14-OSC32_IN_3") (pintype "bidirectional"))
    )
    (net (code "84") (name "unconnected-(U8A-PC15-OSC32_OUT-Pad4)") (class "Default")
      (node (ref "U8") (pin "4") (pinfunction "PC15-OSC32_OUT_4") (pintype "bidirectional"))
    )
  )
)
